# CR-10_Motherboard_1.net
KiCad netlist of a schematic drawn in Altium Designer
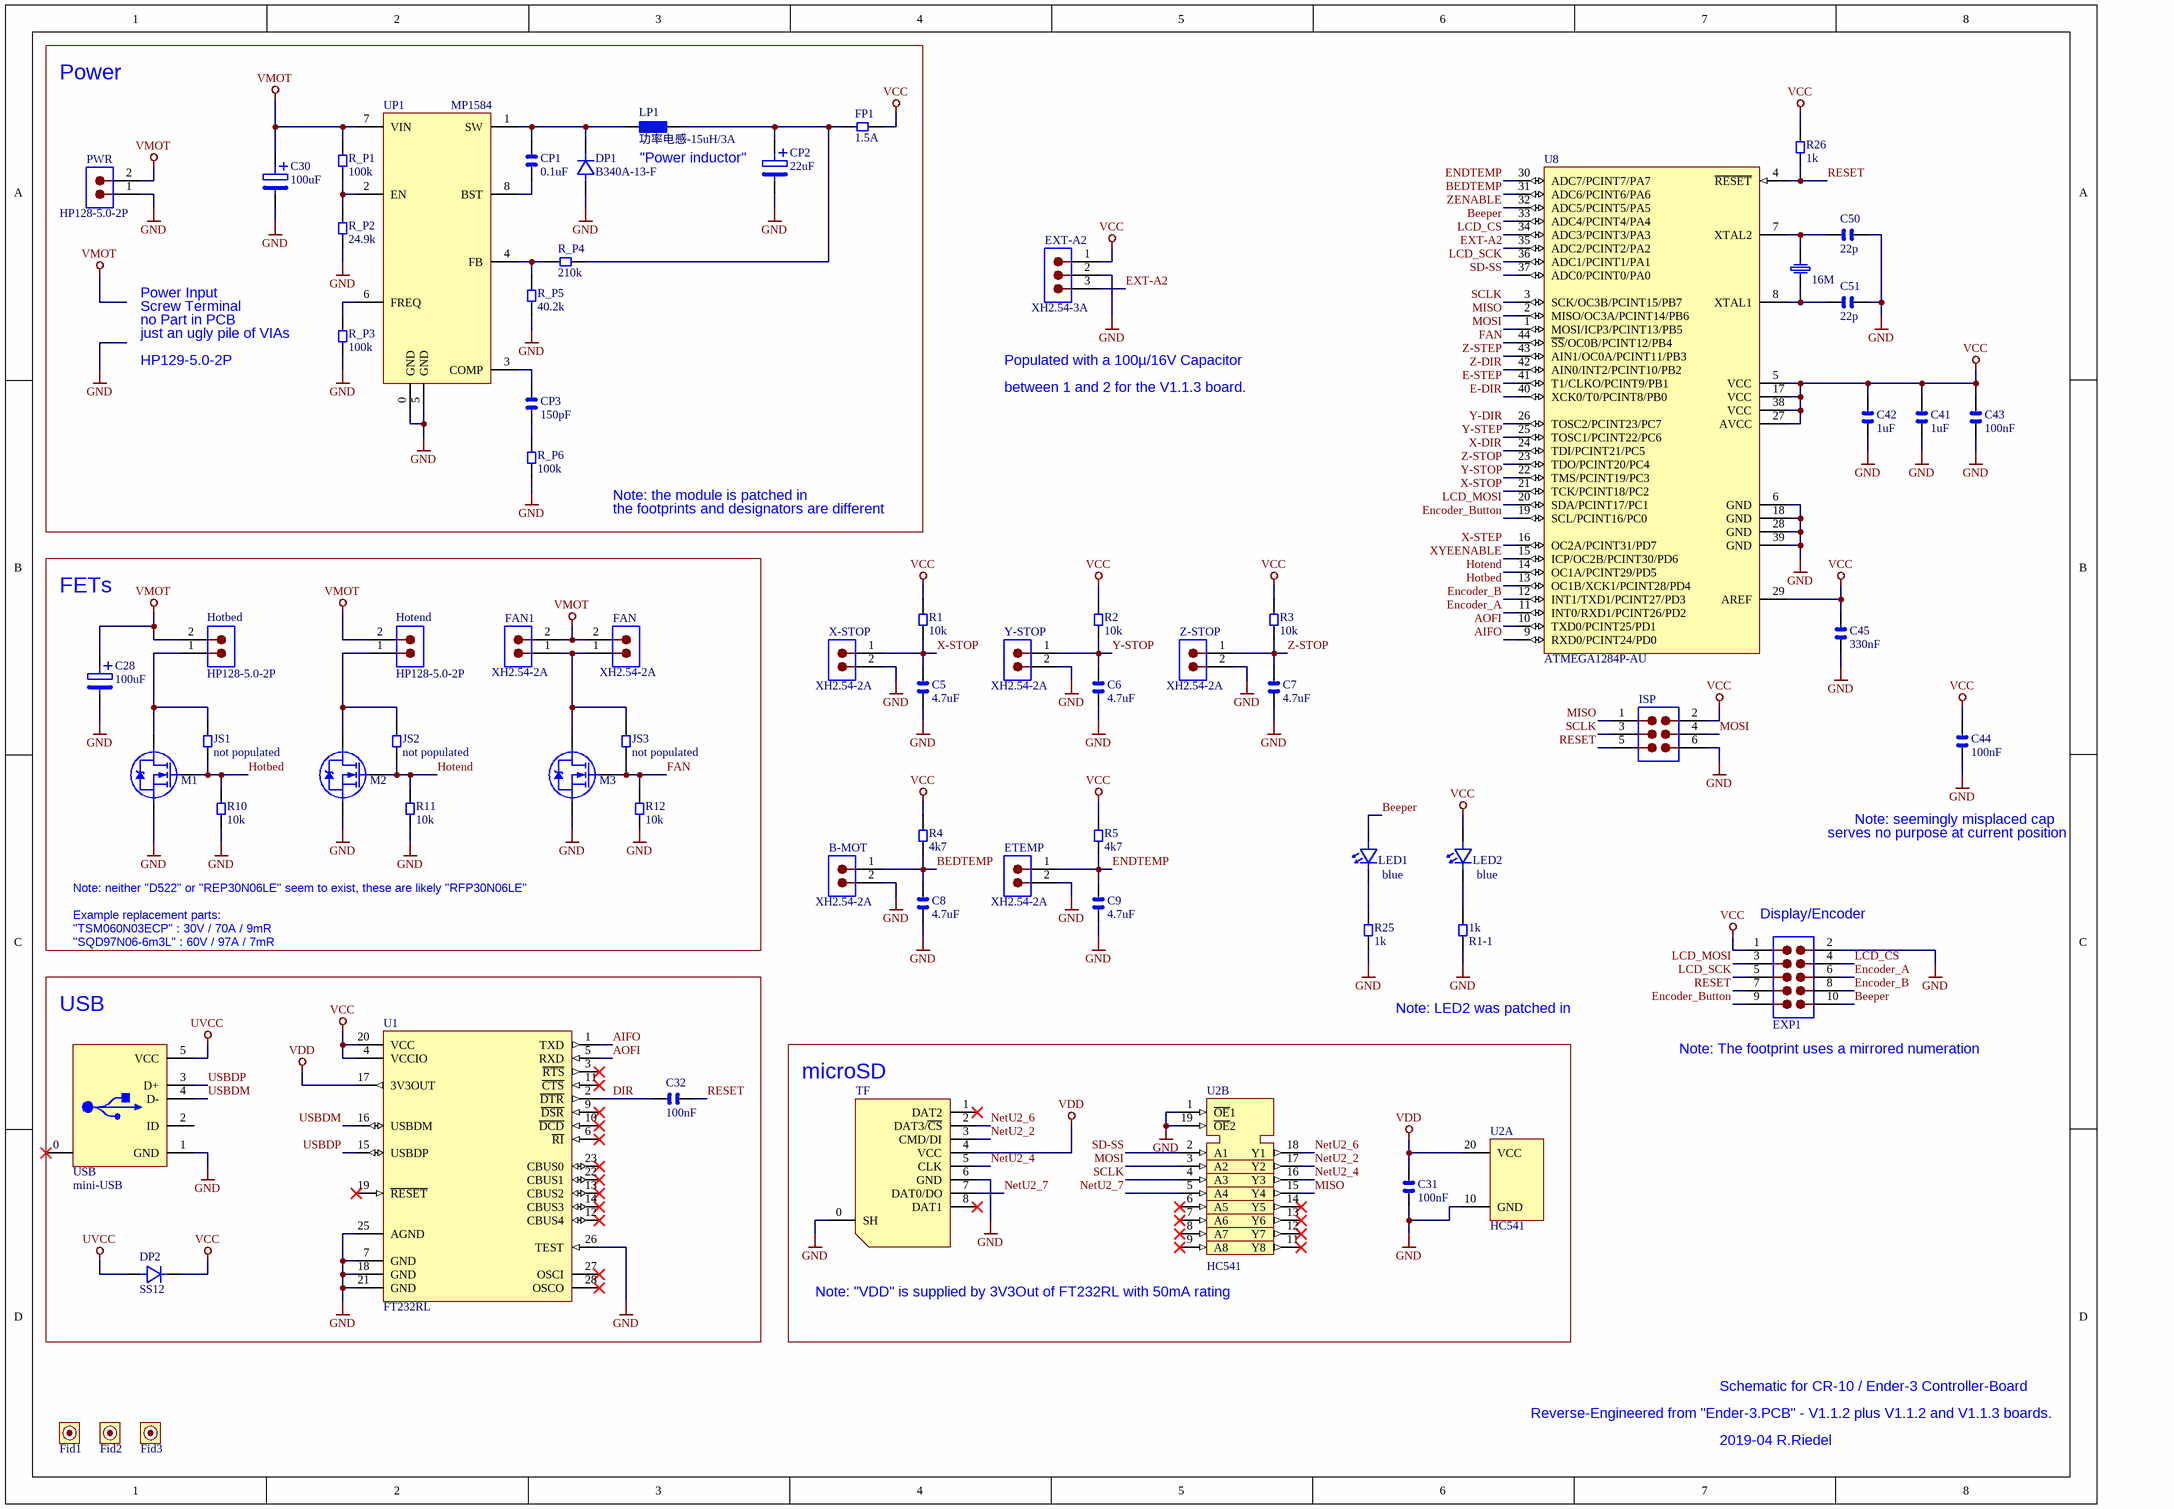
[diagram p0: CR-10 Motherboard_1.SchDoc]

(export (version "E")
  (design (tool "Eeschema 10.0.6"))
  (components
    (comp (ref "1k")
      (value "R1-1")
      (footprint "Ender3:0603")
      (description "0603 Chip Resistor")
      (libsource (lib "CR-10 Motherboard") (part "Resistor"))
    )
    (comp (ref "16M")
      (value "16Mhz")
      (footprint "Ender3:CRY")
      (description "Crystal HC49/US")
      (libsource (lib "CR-10 Motherboard") (part "Crystal"))
    )
    (comp (ref "B-MOT")
      (value "XH2.54-2A")
      (footprint "Ender3:P2")
      (description "Header 1x2")
      (libsource (lib "CR-10 Motherboard") (part "Header 1x2"))
    )
    (comp (ref "C5")
      (value "4.7uF")
      (footprint "Ender3:0805")
      (description "0805 Chip Capacitor")
      (libsource (lib "CR-10 Motherboard") (part "CAP_2_V2"))
    )
    (comp (ref "C6")
      (value "4.7uF")
      (footprint "Ender3:0805")
      (description "0805 Chip Capacitor")
      (libsource (lib "CR-10 Motherboard") (part "CAP_2_V2"))
    )
    (comp (ref "C7")
      (value "4.7uF")
      (footprint "Ender3:0805")
      (description "0805 Chip Capacitor")
      (libsource (lib "CR-10 Motherboard") (part "CAP_2_V2"))
    )
    (comp (ref "C8")
      (value "4.7uF")
      (footprint "Ender3:0805")
      (description "0805 Chip Capacitor")
      (libsource (lib "CR-10 Motherboard") (part "CAP_2_V2"))
    )
    (comp (ref "C9")
      (value "4.7uF")
      (footprint "Ender3:0805")
      (description "0805 Chip Capacitor")
      (libsource (lib "CR-10 Motherboard") (part "CAP_2_V2"))
    )
    (comp (ref "C28")
      (value "100uF")
      (footprint "Ender3:CAP-100")
      (description "Capacitor Polarized")
      (libsource (lib "CR-10 Motherboard") (part "Capacitor Pol"))
    )
    (comp (ref "C30")
      (value "100uF")
      (footprint "Ender3:CAP-100")
      (description "Capacitor Polarized")
      (libsource (lib "CR-10 Motherboard") (part "Capacitor Pol"))
    )
    (comp (ref "C31")
      (value "100nF")
      (footprint "Ender3:0805")
      (description "0805 Chip Capacitor")
      (libsource (lib "CR-10 Motherboard") (part "Capacitor"))
    )
    (comp (ref "C32")
      (value "100nF")
      (footprint "Ender3:0603")
      (description "0805 Chip Capacitor")
      (libsource (lib "CR-10 Motherboard") (part "Capacitor"))
    )
    (comp (ref "C41")
      (value "1uF")
      (footprint "Ender3:0603")
      (description "0805 Chip Capacitor")
      (libsource (lib "CR-10 Motherboard") (part "Capacitor"))
    )
    (comp (ref "C42")
      (value "1uF")
      (footprint "Ender3:0603")
      (description "0805 Chip Capacitor")
      (libsource (lib "CR-10 Motherboard") (part "Capacitor"))
    )
    (comp (ref "C43")
      (value "100nF")
      (footprint "Ender3:0603")
      (description "0805 Chip Capacitor")
      (libsource (lib "CR-10 Motherboard") (part "Capacitor"))
    )
    (comp (ref "C44")
      (value "100nF")
      (footprint "Ender3:0603")
      (description "0805 Chip Capacitor")
      (libsource (lib "CR-10 Motherboard") (part "Capacitor"))
    )
    (comp (ref "C45")
      (value "330nF")
      (footprint "0603")
      (description "0805 Chip Capacitor")
      (libsource (lib "CR-10 Motherboard") (part "Capacitor"))
    )
    (comp (ref "C50")
      (value "22p")
      (footprint "Ender3:0603")
      (description "0805 Chip Capacitor")
      (libsource (lib "CR-10 Motherboard") (part "Capacitor"))
    )
    (comp (ref "C51")
      (value "22p")
      (footprint "Ender3:0603")
      (description "0805 Chip Capacitor")
      (libsource (lib "CR-10 Motherboard") (part "Capacitor"))
    )
    (comp (ref "CP1")
      (value "0.1uF")
      (footprint "Ender3:C0603")
      (description "Chip Capacitor")
      (libsource (lib "CR-10 Motherboard") (part "Capacitor"))
    )
    (comp (ref "CP2")
      (value "22uF")
      (footprint "Ender3:RVT4X5.5")
      (description "Capacitor Polarized")
      (libsource (lib "CR-10 Motherboard") (part "Capacitor Pol"))
    )
    (comp (ref "CP3")
      (value "150pF")
      (footprint "Ender3:C0603")
      (description "Chip Capacitor")
      (libsource (lib "CR-10 Motherboard") (part "Capacitor"))
    )
    (comp (ref "DP1")
      (value "B340A-13-F")
      (footprint "Ender3:D-SMA")
      (description "Diode")
      (libsource (lib "CR-10 Motherboard") (part "Diode_A1_K2"))
    )
    (comp (ref "DP2")
      (value "SS12")
      (footprint "Ender3:D-SMA")
      (description "Diode")
      (libsource (lib "CR-10 Motherboard") (part "Diode_A1_K2"))
    )
    (comp (ref "ETEMP")
      (value "XH2.54-2A")
      (footprint "Ender3:P2")
      (description "Header 1x2")
      (libsource (lib "CR-10 Motherboard") (part "Header 1x2"))
    )
    (comp (ref "EXP1")
      (value "Header 2x5")
      (footprint "Ender3:SOP10")
      (libsource (lib "CR-10 Motherboard") (part "Header 2x5"))
    )
    (comp (ref "EXT-A2")
      (value "XH2.54-3A")
      (footprint "Ender3:XH-3A")
      (description "Header 1x3")
      (libsource (lib "CR-10 Motherboard") (part "Header 1x3"))
    )
    (comp (ref "FAN")
      (value "XH2.54-2A")
      (footprint "Ender3:P2")
      (description "Header 1x2")
      (libsource (lib "CR-10 Motherboard") (part "Header 1x2"))
    )
    (comp (ref "FAN1")
      (value "XH2.54-2A")
      (footprint "Ender3:P2")
      (description "Header 1x2")
      (libsource (lib "CR-10 Motherboard") (part "Header 1x2"))
    )
    (comp (ref "Fid1")
      (value "Fiducial")
      (footprint "Ender3:Fiducial-A")
      (libsource (lib "CR-10 Motherboard") (part "Fiducial"))
    )
    (comp (ref "Fid2")
      (value "Fiducial")
      (footprint "Ender3:Fiducial-A")
      (libsource (lib "CR-10 Motherboard") (part "Fiducial"))
    )
    (comp (ref "Fid3")
      (value "Fiducial")
      (footprint "Ender3:Fiducial-A")
      (libsource (lib "CR-10 Motherboard") (part "Fiducial"))
    )
    (comp (ref "FP1")
      (value "1.5A")
      (footprint "Ender3:MF-MSMF050")
      (description "Chip Resistor")
      (libsource (lib "CR-10 Motherboard") (part "Resistor"))
    )
    (comp (ref "Hotbed")
      (value "HP128-5.0-2P")
      (footprint "CR-10 Motherboard:MOT-2")
      (description "Terminal 1x2")
      (libsource (lib "CR-10 Motherboard") (part "Header 1x2"))
    )
    (comp (ref "Hotend")
      (value "HP128-5.0-2P")
      (footprint "CR-10 Motherboard:MOT-2")
      (description "Terminal 1x2")
      (libsource (lib "CR-10 Motherboard") (part "Header 1x2"))
    )
    (comp (ref "ISP")
      (value "HEADER 3X2")
      (description "Header 2x3")
      (libsource (lib "CR-10 Motherboard") (part "Header 2x3"))
    )
    (comp (ref "JS1")
      (value "not populated")
      (footprint "Ender3:R10")
      (description "0603 Chip Resistor")
      (libsource (lib "CR-10 Motherboard") (part "Resistor"))
    )
    (comp (ref "JS2")
      (value "not populated")
      (footprint "Ender3:R10")
      (description "0603 Chip Resistor")
      (libsource (lib "CR-10 Motherboard") (part "Resistor"))
    )
    (comp (ref "JS3")
      (value "not populated")
      (footprint "Ender3:R10")
      (description "0603 Chip Resistor")
      (libsource (lib "CR-10 Motherboard") (part "Resistor"))
    )
    (comp (ref "LED1")
      (value "blue")
      (footprint "Ender3:0603")
      (description "LED")
      (libsource (lib "CR-10 Motherboard") (part "LED_A1C2"))
    )
    (comp (ref "LED2")
      (value "blue")
      (footprint "Ender3:0603")
      (description "LED")
      (libsource (lib "CR-10 Motherboard") (part "LED_C1A2"))
    )
    (comp (ref "LP1")
      (value "功率电感-15uH/3A")
      (footprint "Ender3:DO3316P")
      (description "Inductor")
      (libsource (lib "CR-10 Motherboard") (part "Inductor"))
    )
    (comp (ref "M1")
      (value "REP30N06LE")
      (footprint "Ender3:TO-252")
      (description "N-FET")
      (libsource (lib "CR-10 Motherboard") (part "N-FET"))
    )
    (comp (ref "M2")
      (value "REP30N06LE")
      (footprint "Ender3:TO-252")
      (description "N-FET")
      (libsource (lib "CR-10 Motherboard") (part "N-FET"))
    )
    (comp (ref "M3")
      (value "REP30N06LE")
      (footprint "Ender3:TO-252")
      (description "N-FET")
      (libsource (lib "CR-10 Motherboard") (part "N-FET"))
    )
    (comp (ref "PWR")
      (value "HP128-5.0-2P")
      (footprint "CR-10 Motherboard:MOT-2")
      (description "Terminal 1x2")
      (libsource (lib "CR-10 Motherboard") (part "Header 1x2"))
    )
    (comp (ref "R1")
      (value "10k")
      (footprint "Ender3:0603")
      (description "0603 Chip Resistor")
      (libsource (lib "CR-10 Motherboard") (part "RES_2_V2"))
    )
    (comp (ref "R2")
      (value "10k")
      (footprint "Ender3:0603")
      (description "0603 Chip Resistor")
      (libsource (lib "CR-10 Motherboard") (part "RES_2_V2"))
    )
    (comp (ref "R3")
      (value "10k")
      (footprint "Ender3:0603")
      (description "0603 Chip Resistor")
      (libsource (lib "CR-10 Motherboard") (part "RES_2_V2"))
    )
    (comp (ref "R4")
      (value "4k7")
      (footprint "Ender3:0603")
      (description "0603 Chip Resistor")
      (libsource (lib "CR-10 Motherboard") (part "RES_2_V2"))
    )
    (comp (ref "R5")
      (value "4k7")
      (footprint "Ender3:0603")
      (description "0603 Chip Resistor")
      (libsource (lib "CR-10 Motherboard") (part "RES_2_V2"))
    )
    (comp (ref "R10")
      (value "10k")
      (footprint "Ender3:0603")
      (description "0603 Chip Resistor")
      (libsource (lib "CR-10 Motherboard") (part "Resistor"))
    )
    (comp (ref "R11")
      (value "10k")
      (footprint "Ender3:0603")
      (description "0603 Chip Resistor")
      (libsource (lib "CR-10 Motherboard") (part "Resistor"))
    )
    (comp (ref "R12")
      (value "10k")
      (footprint "Ender3:0603")
      (description "0603 Chip Resistor")
      (libsource (lib "CR-10 Motherboard") (part "Resistor"))
    )
    (comp (ref "R25")
      (value "1k")
      (footprint "Ender3:0603")
      (description "0603 Chip Resistor")
      (libsource (lib "CR-10 Motherboard") (part "Resistor"))
    )
    (comp (ref "R26")
      (value "1k")
      (footprint "Ender3:0603")
      (description "0603 Chip Resistor")
      (libsource (lib "CR-10 Motherboard") (part "Resistor"))
    )
    (comp (ref "R_P1")
      (value "100k")
      (footprint "Ender3:R0603")
      (description "0603 Chip Resistor")
      (libsource (lib "CR-10 Motherboard") (part "Resistor"))
    )
    (comp (ref "R_P2")
      (value "24.9k")
      (footprint "Ender3:R0603")
      (description "Chip Resistor")
      (libsource (lib "CR-10 Motherboard") (part "Resistor"))
    )
    (comp (ref "R_P3")
      (value "100k")
      (footprint "Ender3:R0603")
      (description "0603 Chip Resistor")
      (libsource (lib "CR-10 Motherboard") (part "Resistor"))
    )
    (comp (ref "R_P4")
      (value "210k")
      (footprint "Ender3:R0603")
      (description "0603 Chip Resistor")
      (libsource (lib "CR-10 Motherboard") (part "Resistor"))
    )
    (comp (ref "R_P5")
      (value "40.2k")
      (footprint "Ender3:R0603")
      (description "0603 Chip Resistor")
      (libsource (lib "CR-10 Motherboard") (part "Resistor"))
    )
    (comp (ref "R_P6")
      (value "100k")
      (footprint "Ender3:R0603")
      (description "0603 Chip Resistor")
      (libsource (lib "CR-10 Motherboard") (part "Resistor"))
    )
    (comp (ref "TF")
      (value "TF")
      (footprint "Ender3:TF")
      (description "microSD")
      (libsource (lib "CR-10 Motherboard") (part "microSD"))
    )
    (comp (ref "U1")
      (value "FT232RL")
      (footprint "Ender3:PL2303")
      (description "FTDI USB UART I.C.")
      (libsource (lib "CR-10 Motherboard") (part "FT232RL"))
    )
    (comp (ref "U2")
      (value "HC541")
      (footprint "Ender3:SSOP-20")
      (description "74HC541 - Octal buffer/line driver")
      (libsource (lib "CR-10 Motherboard") (part "74HC541"))
    )
    (comp (ref "U8")
      (value "ATMEGA1284P-AU")
      (footprint "Ender3:QFP-44")
      (description "AVR 8-Bit, 128k FLASH, TQFP44")
      (fields (field (name "PART NUMBER") "ATmega1284P-AU"))
      (libsource (lib "CR-10 Motherboard") (part "ATmegaxx4PA-xx"))
    )
    (comp (ref "UP1")
      (value "MP1584")
      (footprint "Ender3:SOIC8E")
      (libsource (lib "CR-10 Motherboard") (part "MP1584"))
    )
    (comp (ref "USB")
      (value "mini-USB")
      (footprint "Ender3:USB")
      (description "USB")
      (libsource (lib "CR-10 Motherboard") (part "USB"))
    )
    (comp (ref "X-STOP")
      (value "XH2.54-2A")
      (footprint "Ender3:P2")
      (description "Header 1x2")
      (libsource (lib "CR-10 Motherboard") (part "Header 1x2"))
    )
    (comp (ref "Y-STOP")
      (value "XH2.54-2A")
      (footprint "Ender3:P2")
      (description "Header 1x2")
      (libsource (lib "CR-10 Motherboard") (part "Header 1x2"))
    )
    (comp (ref "Z-STOP")
      (value "XH2.54-2A")
      (footprint "Ender3:P2")
      (description "Header 1x2")
      (libsource (lib "CR-10 Motherboard") (part "Header 1x2"))
    )
  )
  (nets
    (net (code "1") (name "/AIFO") (class "Default")
      (node (ref "U1") (pin "1") (pinfunction "TXD_1") (pintype "output"))
      (node (ref "U8") (pin "9") (pinfunction "RXD0/PCINT24/PD0_9") (pintype "bidirectional"))
    )
    (net (code "2") (name "/AOFI") (class "Default")
      (node (ref "U1") (pin "5") (pinfunction "RXD_5") (pintype "input"))
      (node (ref "U8") (pin "10") (pinfunction "TXD0/PCINT25/PD1_10") (pintype "bidirectional"))
    )
    (net (code "3") (name "/BEDTEMP") (class "Default")
      (node (ref "B-MOT") (pin "1") (pinfunction "1_1") (pintype "passive"))
      (node (ref "C8") (pin "1") (pinfunction "1_1") (pintype "passive"))
      (node (ref "R4") (pin "1") (pinfunction "1_1") (pintype "passive"))
      (node (ref "U8") (pin "31") (pinfunction "ADC6/PCINT6/PA6_31") (pintype "bidirectional"))
    )
    (net (code "4") (name "/Beeper") (class "Default")
      (node (ref "EXP1") (pin "10") (pinfunction "10_10") (pintype "passive"))
      (node (ref "LED1") (pin "1") (pinfunction "1_1") (pintype "passive"))
      (node (ref "U8") (pin "33") (pinfunction "ADC4/PCINT4/PA4_33") (pintype "bidirectional"))
    )
    (net (code "5") (name "/DIR") (class "Default")
      (node (ref "C32") (pin "1") (pinfunction "1_1") (pintype "passive"))
      (node (ref "U1") (pin "2") (pinfunction "~{DTR}_2") (pintype "output"))
    )
    (net (code "6") (name "/E-DIR") (class "Default")
      (node (ref "U8") (pin "40") (pinfunction "XCK0/T0/PCINT8/PB0_40") (pintype "bidirectional"))
    )
    (net (code "7") (name "/E-STEP") (class "Default")
      (node (ref "U8") (pin "41") (pinfunction "T1/CLKO/PCINT9/PB1_41") (pintype "bidirectional"))
    )
    (net (code "8") (name "/ENDTEMP") (class "Default")
      (node (ref "C9") (pin "1") (pinfunction "1_1") (pintype "passive"))
      (node (ref "ETEMP") (pin "1") (pinfunction "1_1") (pintype "passive"))
      (node (ref "R5") (pin "1") (pinfunction "1_1") (pintype "passive"))
      (node (ref "U8") (pin "30") (pinfunction "ADC7/PCINT7/PA7_30") (pintype "bidirectional"))
    )
    (net (code "9") (name "/EXT-A2") (class "Default")
      (node (ref "EXT-A2") (pin "3") (pinfunction "3_3") (pintype "passive"))
      (node (ref "U8") (pin "35") (pinfunction "ADC2/PCINT2/PA2_35") (pintype "bidirectional"))
    )
    (net (code "10") (name "/Encoder_A") (class "Default")
      (node (ref "EXP1") (pin "6") (pinfunction "6_6") (pintype "passive"))
      (node (ref "U8") (pin "11") (pinfunction "INT0/RXD1/PCINT26/PD2_11") (pintype "bidirectional"))
    )
    (net (code "11") (name "/Encoder_B") (class "Default")
      (node (ref "EXP1") (pin "8") (pinfunction "8_8") (pintype "passive"))
      (node (ref "U8") (pin "12") (pinfunction "INT1/TXD1/PCINT27/PD3_12") (pintype "bidirectional"))
    )
    (net (code "12") (name "/Encoder_Button") (class "Default")
      (node (ref "EXP1") (pin "9") (pinfunction "9_9") (pintype "passive"))
      (node (ref "U8") (pin "19") (pinfunction "SCL/PCINT16/PC0_19") (pintype "bidirectional"))
    )
    (net (code "13") (name "/FAN") (class "Default")
      (node (ref "JS3") (pin "1") (pinfunction "1_1") (pintype "passive"))
      (node (ref "M3") (pin "1") (pinfunction "G_1") (pintype "passive"))
      (node (ref "R12") (pin "1") (pinfunction "1_1") (pintype "passive"))
      (node (ref "U8") (pin "44") (pinfunction "~{SS}/OC0B/PCINT12/PB4_44") (pintype "bidirectional"))
    )
    (net (code "14") (name "/Hotbed") (class "Default")
      (node (ref "JS1") (pin "1") (pinfunction "1_1") (pintype "passive"))
      (node (ref "M1") (pin "1") (pinfunction "G_1") (pintype "passive"))
      (node (ref "R10") (pin "1") (pinfunction "1_1") (pintype "passive"))
      (node (ref "U8") (pin "13") (pinfunction "OC1B/XCK1/PCINT28/PD4_13") (pintype "bidirectional"))
    )
    (net (code "15") (name "/Hotend") (class "Default")
      (node (ref "JS2") (pin "1") (pinfunction "1_1") (pintype "passive"))
      (node (ref "M2") (pin "1") (pinfunction "G_1") (pintype "passive"))
      (node (ref "R11") (pin "1") (pinfunction "1_1") (pintype "passive"))
      (node (ref "U8") (pin "14") (pinfunction "OC1A/PCINT29/PD5_14") (pintype "bidirectional"))
    )
    (net (code "16") (name "/LCD_CS") (class "Default")
      (node (ref "EXP1") (pin "4") (pinfunction "4_4") (pintype "passive"))
      (node (ref "U8") (pin "34") (pinfunction "ADC3/PCINT3/PA3_34") (pintype "bidirectional"))
    )
    (net (code "17") (name "/LCD_MOSI") (class "Default")
      (node (ref "EXP1") (pin "3") (pinfunction "3_3") (pintype "passive"))
      (node (ref "U8") (pin "20") (pinfunction "SDA/PCINT17/PC1_20") (pintype "bidirectional"))
    )
    (net (code "18") (name "/LCD_SCK") (class "Default")
      (node (ref "EXP1") (pin "5") (pinfunction "5_5") (pintype "passive"))
      (node (ref "U8") (pin "36") (pinfunction "ADC1/PCINT1/PA1_36") (pintype "bidirectional"))
    )
    (net (code "19") (name "/MISO") (class "Default")
      (node (ref "ISP") (pin "1") (pinfunction "1_1") (pintype "passive"))
      (node (ref "U2") (pin "15") (pinfunction "Y4_15") (pintype "output"))
      (node (ref "U8") (pin "2") (pinfunction "MISO/OC3A/PCINT14/PB6_2") (pintype "bidirectional"))
    )
    (net (code "20") (name "/MOSI") (class "Default")
      (node (ref "ISP") (pin "4") (pinfunction "4_4") (pintype "passive"))
      (node (ref "U2") (pin "3") (pinfunction "A2_3") (pintype "input"))
      (node (ref "U8") (pin "1") (pinfunction "MOSI/ICP3/PCINT13/PB5_1") (pintype "bidirectional"))
    )
    (net (code "21") (name "/NetU2_2") (class "Default")
      (node (ref "TF") (pin "3") (pinfunction "CMD/DI_3") (pintype "passive"))
      (node (ref "U2") (pin "17") (pinfunction "Y2_17") (pintype "output"))
    )
    (net (code "22") (name "/NetU2_4") (class "Default")
      (node (ref "TF") (pin "5") (pinfunction "CLK_5") (pintype "passive"))
      (node (ref "U2") (pin "16") (pinfunction "Y3_16") (pintype "output"))
    )
    (net (code "23") (name "/NetU2_6") (class "Default")
      (node (ref "TF") (pin "2") (pinfunction "DAT3/~{CS}_2") (pintype "passive"))
      (node (ref "U2") (pin "18") (pinfunction "Y1_18") (pintype "output"))
    )
    (net (code "24") (name "/NetU2_7") (class "Default")
      (node (ref "TF") (pin "7") (pinfunction "DAT0/DO_7") (pintype "passive"))
      (node (ref "U2") (pin "5") (pinfunction "A4_5") (pintype "input"))
    )
    (net (code "25") (name "/RESET") (class "Default")
      (node (ref "C32") (pin "2") (pinfunction "2_2") (pintype "passive"))
      (node (ref "EXP1") (pin "7") (pinfunction "7_7") (pintype "passive"))
      (node (ref "ISP") (pin "5") (pinfunction "5_5") (pintype "passive"))
      (node (ref "R26") (pin "1") (pinfunction "1_1") (pintype "passive"))
      (node (ref "U8") (pin "4") (pinfunction "~{RESET}_4") (pintype "input"))
    )
    (net (code "26") (name "/SCLK") (class "Default")
      (node (ref "ISP") (pin "3") (pinfunction "3_3") (pintype "passive"))
      (node (ref "U2") (pin "4") (pinfunction "A3_4") (pintype "input"))
      (node (ref "U8") (pin "3") (pinfunction "SCK/OC3B/PCINT15/PB7_3") (pintype "bidirectional"))
    )
    (net (code "27") (name "/SD-SS") (class "Default")
      (node (ref "U2") (pin "2") (pinfunction "A1_2") (pintype "input"))
      (node (ref "U8") (pin "37") (pinfunction "ADC0/PCINT0/PA0_37") (pintype "bidirectional"))
    )
    (net (code "28") (name "/USBDM") (class "Default")
      (node (ref "U1") (pin "16") (pinfunction "USBDM_16") (pintype "bidirectional"))
      (node (ref "USB") (pin "4") (pinfunction "D-_4") (pintype "passive"))
    )
    (net (code "29") (name "/USBDP") (class "Default")
      (node (ref "U1") (pin "15") (pinfunction "USBDP_15") (pintype "bidirectional"))
      (node (ref "USB") (pin "3") (pinfunction "D+_3") (pintype "passive"))
    )
    (net (code "30") (name "/X-DIR") (class "Default")
      (node (ref "U8") (pin "24") (pinfunction "TDI/PCINT21/PC5_24") (pintype "bidirectional"))
    )
    (net (code "31") (name "/X-STEP") (class "Default")
      (node (ref "U8") (pin "16") (pinfunction "OC2A/PCINT31/PD7_16") (pintype "bidirectional"))
    )
    (net (code "32") (name "/X-STOP") (class "Default")
      (node (ref "C5") (pin "1") (pinfunction "1_1") (pintype "passive"))
      (node (ref "R1") (pin "1") (pinfunction "1_1") (pintype "passive"))
      (node (ref "U8") (pin "21") (pinfunction "TCK/PCINT18/PC2_21") (pintype "bidirectional"))
      (node (ref "X-STOP") (pin "1") (pinfunction "1_1") (pintype "passive"))
    )
    (net (code "33") (name "/XYEENABLE") (class "Default")
      (node (ref "U8") (pin "15") (pinfunction "ICP/OC2B/PCINT30/PD6_15") (pintype "bidirectional"))
    )
    (net (code "34") (name "/Y-DIR") (class "Default")
      (node (ref "U8") (pin "26") (pinfunction "TOSC2/PCINT23/PC7_26") (pintype "bidirectional"))
    )
    (net (code "35") (name "/Y-STEP") (class "Default")
      (node (ref "U8") (pin "25") (pinfunction "TOSC1/PCINT22/PC6_25") (pintype "bidirectional"))
    )
    (net (code "36") (name "/Y-STOP") (class "Default")
      (node (ref "C6") (pin "1") (pinfunction "1_1") (pintype "passive"))
      (node (ref "R2") (pin "1") (pinfunction "1_1") (pintype "passive"))
      (node (ref "U8") (pin "22") (pinfunction "TMS/PCINT19/PC3_22") (pintype "bidirectional"))
      (node (ref "Y-STOP") (pin "1") (pinfunction "1_1") (pintype "passive"))
    )
    (net (code "37") (name "/Z-DIR") (class "Default")
      (node (ref "U8") (pin "42") (pinfunction "AIN0/INT2/PCINT10/PB2_42") (pintype "bidirectional"))
    )
    (net (code "38") (name "/Z-STEP") (class "Default")
      (node (ref "U8") (pin "43") (pinfunction "AIN1/OC0A/PCINT11/PB3_43") (pintype "bidirectional"))
    )
    (net (code "39") (name "/Z-STOP") (class "Default")
      (node (ref "C7") (pin "1") (pinfunction "1_1") (pintype "passive"))
      (node (ref "R3") (pin "1") (pinfunction "1_1") (pintype "passive"))
      (node (ref "U8") (pin "23") (pinfunction "TDO/PCINT20/PC4_23") (pintype "bidirectional"))
      (node (ref "Z-STOP") (pin "1") (pinfunction "1_1") (pintype "passive"))
    )
    (net (code "40") (name "/ZENABLE") (class "Default")
      (node (ref "U8") (pin "32") (pinfunction "ADC5/PCINT5/PA5_32") (pintype "bidirectional"))
    )
    (net (code "41") (name "GND") (class "Default")
      (node (ref "1k") (pin "2") (pinfunction "2_2") (pintype "passive"))
      (node (ref "B-MOT") (pin "2") (pinfunction "2_2") (pintype "passive"))
      (node (ref "C28") (pin "2") (pinfunction "2_2") (pintype "passive"))
      (node (ref "C30") (pin "2") (pinfunction "2_2") (pintype "passive"))
      (node (ref "C31") (pin "2") (pinfunction "2_2") (pintype "passive"))
      (node (ref "C41") (pin "2") (pinfunction "2_2") (pintype "passive"))
      (node (ref "C42") (pin "2") (pinfunction "2_2") (pintype "passive"))
      (node (ref "C43") (pin "2") (pinfunction "2_2") (pintype "passive"))
      (node (ref "C44") (pin "2") (pinfunction "2_2") (pintype "passive"))
      (node (ref "C45") (pin "2") (pinfunction "2_2") (pintype "passive"))
      (node (ref "C5") (pin "2") (pinfunction "2_2") (pintype "passive"))
      (node (ref "C50") (pin "2") (pinfunction "2_2") (pintype "passive"))
      (node (ref "C51") (pin "2") (pinfunction "2_2") (pintype "passive"))
      (node (ref "C6") (pin "2") (pinfunction "2_2") (pintype "passive"))
      (node (ref "C7") (pin "2") (pinfunction "2_2") (pintype "passive"))
      (node (ref "C8") (pin "2") (pinfunction "2_2") (pintype "passive"))
      (node (ref "C9") (pin "2") (pinfunction "2_2") (pintype "passive"))
      (node (ref "CP2") (pin "2") (pinfunction "2_2") (pintype "passive"))
      (node (ref "DP1") (pin "1") (pinfunction "1_1") (pintype "passive"))
      (node (ref "ETEMP") (pin "2") (pinfunction "2_2") (pintype "passive"))
      (node (ref "EXP1") (pin "2") (pinfunction "2_2") (pintype "passive"))
      (node (ref "EXT-A2") (pin "2") (pinfunction "2_2") (pintype "passive"))
      (node (ref "ISP") (pin "6") (pinfunction "6_6") (pintype "passive"))
      (node (ref "M1") (pin "3") (pinfunction "S_3") (pintype "passive"))
      (node (ref "M2") (pin "3") (pinfunction "S_3") (pintype "passive"))
      (node (ref "M3") (pin "3") (pinfunction "S_3") (pintype "passive"))
      (node (ref "PWR") (pin "1") (pinfunction "1_1") (pintype "passive"))
      (node (ref "R10") (pin "2") (pinfunction "2_2") (pintype "passive"))
      (node (ref "R11") (pin "2") (pinfunction "2_2") (pintype "passive"))
      (node (ref "R12") (pin "2") (pinfunction "2_2") (pintype "passive"))
      (node (ref "R25") (pin "2") (pinfunction "2_2") (pintype "passive"))
      (node (ref "R_P2") (pin "2") (pinfunction "2_2") (pintype "passive"))
      (node (ref "R_P3") (pin "2") (pinfunction "2_2") (pintype "passive"))
      (node (ref "R_P5") (pin "2") (pinfunction "2_2") (pintype "passive"))
      (node (ref "R_P6") (pin "2") (pinfunction "2_2") (pintype "passive"))
      (node (ref "TF") (pin "0") (pinfunction "SH_0") (pintype "passive"))
      (node (ref "TF") (pin "6") (pinfunction "GND_6") (pintype "passive"))
      (node (ref "U1") (pin "18") (pinfunction "GND_18") (pintype "power_in"))
      (node (ref "U1") (pin "21") (pinfunction "GND_21") (pintype "power_in"))
      (node (ref "U1") (pin "25") (pinfunction "AGND_25") (pintype "power_in"))
      (node (ref "U1") (pin "26") (pinfunction "TEST_26") (pintype "input"))
      (node (ref "U1") (pin "7") (pinfunction "GND_7") (pintype "power_in"))
      (node (ref "U2") (pin "1") (pinfunction "~{OE}1_1") (pintype "input"))
      (node (ref "U2") (pin "10") (pinfunction "GND_10") (pintype "power_in"))
      (node (ref "U2") (pin "19") (pinfunction "~{OE}2_19") (pintype "input"))
      (node (ref "U8") (pin "18") (pinfunction "GND_18") (pintype "power_in"))
      (node (ref "U8") (pin "28") (pinfunction "GND_28") (pintype "power_in"))
      (node (ref "U8") (pin "39") (pinfunction "GND_39") (pintype "power_in"))
      (node (ref "U8") (pin "6") (pinfunction "GND_6") (pintype "power_in"))
      (node (ref "UP1") (pin "0") (pinfunction "GND_0") (pintype "passive"))
      (node (ref "UP1") (pin "5") (pinfunction "GND_5") (pintype "passive"))
      (node (ref "USB") (pin "1") (pinfunction "GND_1") (pintype "passive"))
      (node (ref "X-STOP") (pin "2") (pinfunction "2_2") (pintype "passive"))
      (node (ref "Y-STOP") (pin "2") (pinfunction "2_2") (pintype "passive"))
      (node (ref "Z-STOP") (pin "2") (pinfunction "2_2") (pintype "passive"))
    )
    (net (code "42") (name "Net-(1k-Pad1)") (class "Default")
      (node (ref "1k") (pin "1") (pinfunction "1_1") (pintype "passive"))
      (node (ref "LED2") (pin "1") (pinfunction "1_1") (pintype "passive"))
    )
    (net (code "43") (name "Net-(CP2-Pad1)") (class "Default")
      (node (ref "CP2") (pin "1") (pinfunction "1_1") (pintype "passive"))
      (node (ref "FP1") (pin "1") (pinfunction "1_1") (pintype "passive"))
      (node (ref "LP1") (pin "1") (pinfunction "1_1") (pintype "passive"))
      (node (ref "R_P4") (pin "2") (pinfunction "2_2") (pintype "passive"))
    )
    (net (code "44") (name "Net-(CP3-Pad1)") (class "Default")
      (node (ref "CP3") (pin "1") (pinfunction "1_1") (pintype "passive"))
      (node (ref "R_P6") (pin "1") (pinfunction "1_1") (pintype "passive"))
    )
    (net (code "45") (name "Net-(LED1-Pad2)") (class "Default")
      (node (ref "LED1") (pin "2") (pinfunction "2_2") (pintype "passive"))
      (node (ref "R25") (pin "1") (pinfunction "1_1") (pintype "passive"))
    )
    (net (code "46") (name "Net-(M1-D)") (class "Default")
      (node (ref "Hotbed") (pin "1") (pinfunction "1_1") (pintype "passive"))
      (node (ref "JS1") (pin "2") (pinfunction "2_2") (pintype "passive"))
      (node (ref "M1") (pin "2") (pinfunction "D_2") (pintype "passive"))
    )
    (net (code "47") (name "Net-(M2-D)") (class "Default")
      (node (ref "Hotend") (pin "1") (pinfunction "1_1") (pintype "passive"))
      (node (ref "JS2") (pin "2") (pinfunction "2_2") (pintype "passive"))
      (node (ref "M2") (pin "2") (pinfunction "D_2") (pintype "passive"))
    )
    (net (code "48") (name "Net-(M3-D)") (class "Default")
      (node (ref "FAN") (pin "1") (pinfunction "1_1") (pintype "passive"))
      (node (ref "FAN1") (pin "1") (pinfunction "1_1") (pintype "passive"))
      (node (ref "JS3") (pin "2") (pinfunction "2_2") (pintype "passive"))
      (node (ref "M3") (pin "2") (pinfunction "D_2") (pintype "passive"))
    )
    (net (code "49") (name "Net-(U8-XTAL1)") (class "Default")
      (node (ref "16M") (pin "2") (pinfunction "2_2") (pintype "passive"))
      (node (ref "C51") (pin "1") (pinfunction "1_1") (pintype "passive"))
      (node (ref "U8") (pin "8") (pinfunction "XTAL1_8") (pintype "passive"))
    )
    (net (code "50") (name "Net-(U8-XTAL2)") (class "Default")
      (node (ref "16M") (pin "1") (pinfunction "1_1") (pintype "passive"))
      (node (ref "C50") (pin "1") (pinfunction "1_1") (pintype "passive"))
      (node (ref "U8") (pin "7") (pinfunction "XTAL2_7") (pintype "passive"))
    )
    (net (code "51") (name "Net-(UP1-BST)") (class "Default")
      (node (ref "CP1") (pin "1") (pinfunction "1_1") (pintype "passive"))
      (node (ref "UP1") (pin "8") (pinfunction "BST_8") (pintype "passive"))
    )
    (net (code "52") (name "Net-(UP1-COMP)") (class "Default")
      (node (ref "CP3") (pin "2") (pinfunction "2_2") (pintype "passive"))
      (node (ref "UP1") (pin "3") (pinfunction "COMP_3") (pintype "passive"))
    )
    (net (code "53") (name "Net-(UP1-EN)") (class "Default")
      (node (ref "R_P1") (pin "2") (pinfunction "2_2") (pintype "passive"))
      (node (ref "R_P2") (pin "1") (pinfunction "1_1") (pintype "passive"))
      (node (ref "UP1") (pin "2") (pinfunction "EN_2") (pintype "passive"))
    )
    (net (code "54") (name "Net-(UP1-FB)") (class "Default")
      (node (ref "R_P4") (pin "1") (pinfunction "1_1") (pintype "passive"))
      (node (ref "R_P5") (pin "1") (pinfunction "1_1") (pintype "passive"))
      (node (ref "UP1") (pin "4") (pinfunction "FB_4") (pintype "passive"))
    )
    (net (code "55") (name "Net-(UP1-FREQ)") (class "Default")
      (node (ref "R_P3") (pin "1") (pinfunction "1_1") (pintype "passive"))
      (node (ref "UP1") (pin "6") (pinfunction "FREQ_6") (pintype "passive"))
    )
    (net (code "56") (name "Net-(UP1-SW)") (class "Default")
      (node (ref "CP1") (pin "2") (pinfunction "2_2") (pintype "passive"))
      (node (ref "DP1") (pin "2") (pinfunction "2_2") (pintype "passive"))
      (node (ref "LP1") (pin "2") (pinfunction "2_2") (pintype "passive"))
      (node (ref "UP1") (pin "1") (pinfunction "SW_1") (pintype "passive"))
    )
    (net (code "57") (name "UVCC") (class "Default")
      (node (ref "DP2") (pin "1") (pinfunction "1_1") (pintype "passive"))
      (node (ref "USB") (pin "5") (pinfunction "VCC_5") (pintype "passive"))
    )
    (net (code "58") (name "VCC") (class "Default")
      (node (ref "C41") (pin "1") (pinfunction "1_1") (pintype "passive"))
      (node (ref "C42") (pin "1") (pinfunction "1_1") (pintype "passive"))
      (node (ref "C43") (pin "1") (pinfunction "1_1") (pintype "passive"))
      (node (ref "C44") (pin "1") (pinfunction "1_1") (pintype "passive"))
      (node (ref "C45") (pin "1") (pinfunction "1_1") (pintype "passive"))
      (node (ref "DP2") (pin "2") (pinfunction "2_2") (pintype "passive"))
      (node (ref "EXP1") (pin "1") (pinfunction "1_1") (pintype "passive"))
      (node (ref "EXT-A2") (pin "1") (pinfunction "1_1") (pintype "passive"))
      (node (ref "FP1") (pin "2") (pinfunction "2_2") (pintype "passive"))
      (node (ref "ISP") (pin "2") (pinfunction "2_2") (pintype "passive"))
      (node (ref "LED2") (pin "2") (pinfunction "2_2") (pintype "passive"))
      (node (ref "R1") (pin "2") (pinfunction "2_2") (pintype "passive"))
      (node (ref "R2") (pin "2") (pinfunction "2_2") (pintype "passive"))
      (node (ref "R26") (pin "2") (pinfunction "2_2") (pintype "passive"))
      (node (ref "R3") (pin "2") (pinfunction "2_2") (pintype "passive"))
      (node (ref "R4") (pin "2") (pinfunction "2_2") (pintype "passive"))
      (node (ref "R5") (pin "2") (pinfunction "2_2") (pintype "passive"))
      (node (ref "U1") (pin "20") (pinfunction "VCC_20") (pintype "power_in"))
      (node (ref "U1") (pin "4") (pinfunction "VCCIO_4") (pintype "power_in"))
      (node (ref "U8") (pin "17") (pinfunction "VCC_17") (pintype "power_in"))
      (node (ref "U8") (pin "27") (pinfunction "AVCC_27") (pintype "power_in"))
      (node (ref "U8") (pin "29") (pinfunction "AREF_29") (pintype "passive"))
      (node (ref "U8") (pin "38") (pinfunction "VCC_38") (pintype "power_in"))
      (node (ref "U8") (pin "5") (pinfunction "VCC_5") (pintype "power_in"))
    )
    (net (code "59") (name "VDD") (class "Default")
      (node (ref "C31") (pin "1") (pinfunction "1_1") (pintype "passive"))
      (node (ref "TF") (pin "4") (pinfunction "VCC_4") (pintype "passive"))
      (node (ref "U1") (pin "17") (pinfunction "3V3OUT_17") (pintype "output"))
      (node (ref "U2") (pin "20") (pinfunction "VCC_20") (pintype "power_in"))
    )
    (net (code "60") (name "VMOT") (class "Default")
      (node (ref "C28") (pin "1") (pinfunction "1_1") (pintype "passive"))
      (node (ref "C30") (pin "1") (pinfunction "1_1") (pintype "passive"))
      (node (ref "FAN") (pin "2") (pinfunction "2_2") (pintype "passive"))
      (node (ref "FAN1") (pin "2") (pinfunction "2_2") (pintype "passive"))
      (node (ref "Hotbed") (pin "2") (pinfunction "2_2") (pintype "passive"))
      (node (ref "Hotend") (pin "2") (pinfunction "2_2") (pintype "passive"))
      (node (ref "PWR") (pin "2") (pinfunction "2_2") (pintype "passive"))
      (node (ref "R_P1") (pin "1") (pinfunction "1_1") (pintype "passive"))
      (node (ref "UP1") (pin "7") (pinfunction "VIN_7") (pintype "passive"))
    )
    (net (code "61") (name "unconnected-(TF-DAT1-Pad8)") (class "Default")
      (node (ref "TF") (pin "8") (pinfunction "DAT1_8") (pintype "passive+no_connect"))
    )
    (net (code "62") (name "unconnected-(TF-DAT2-Pad1)") (class "Default")
      (node (ref "TF") (pin "1") (pinfunction "DAT2_1") (pintype "passive+no_connect"))
    )
    (net (code "63") (name "unconnected-(U1-CBUS0-Pad23)") (class "Default")
      (node (ref "U1") (pin "23") (pinfunction "CBUS0_23") (pintype "bidirectional+no_connect"))
    )
    (net (code "64") (name "unconnected-(U1-CBUS1-Pad22)") (class "Default")
      (node (ref "U1") (pin "22") (pinfunction "CBUS1_22") (pintype "bidirectional+no_connect"))
    )
    (net (code "65") (name "unconnected-(U1-CBUS2-Pad13)") (class "Default")
      (node (ref "U1") (pin "13") (pinfunction "CBUS2_13") (pintype "bidirectional+no_connect"))
    )
    (net (code "66") (name "unconnected-(U1-CBUS3-Pad14)") (class "Default")
      (node (ref "U1") (pin "14") (pinfunction "CBUS3_14") (pintype "bidirectional+no_connect"))
    )
    (net (code "67") (name "unconnected-(U1-CBUS4-Pad12)") (class "Default")
      (node (ref "U1") (pin "12") (pinfunction "CBUS4_12") (pintype "bidirectional+no_connect"))
    )
    (net (code "68") (name "unconnected-(U1-OSCI-Pad27)") (class "Default")
      (node (ref "U1") (pin "27") (pinfunction "OSCI_27") (pintype "power_in+no_connect"))
    )
    (net (code "69") (name "unconnected-(U1-OSCO-Pad28)") (class "Default")
      (node (ref "U1") (pin "28") (pinfunction "OSCO_28") (pintype "power_in+no_connect"))
    )
    (net (code "70") (name "unconnected-(U1-~{CTS}-Pad11)") (class "Default")
      (node (ref "U1") (pin "11") (pinfunction "~{CTS}_11") (pintype "input+no_connect"))
    )
    (net (code "71") (name "unconnected-(U1-~{DCD}-Pad10)") (class "Default")
      (node (ref "U1") (pin "10") (pinfunction "~{DCD}_10") (pintype "input+no_connect"))
    )
    (net (code "72") (name "unconnected-(U1-~{DSR}-Pad9)") (class "Default")
      (node (ref "U1") (pin "9") (pinfunction "~{DSR}_9") (pintype "input+no_connect"))
    )
    (net (code "73") (name "unconnected-(U1-~{RESET}-Pad19)") (class "Default")
      (node (ref "U1") (pin "19") (pinfunction "~{RESET}_19") (pintype "input+no_connect"))
    )
    (net (code "74") (name "unconnected-(U1-~{RI}-Pad6)") (class "Default")
      (node (ref "U1") (pin "6") (pinfunction "~{RI}_6") (pintype "input+no_connect"))
    )
    (net (code "75") (name "unconnected-(U1-~{RTS}-Pad3)") (class "Default")
      (node (ref "U1") (pin "3") (pinfunction "~{RTS}_3") (pintype "output+no_connect"))
    )
    (net (code "76") (name "unconnected-(U2B-A5-Pad6)") (class "Default")
      (node (ref "U2") (pin "6") (pinfunction "A5_6") (pintype "input+no_connect"))
    )
    (net (code "77") (name "unconnected-(U2B-A6-Pad7)") (class "Default")
      (node (ref "U2") (pin "7") (pinfunction "A6_7") (pintype "input+no_connect"))
    )
    (net (code "78") (name "unconnected-(U2B-A7-Pad8)") (class "Default")
      (node (ref "U2") (pin "8") (pinfunction "A7_8") (pintype "input+no_connect"))
    )
    (net (code "79") (name "unconnected-(U2B-A8-Pad9)") (class "Default")
      (node (ref "U2") (pin "9") (pinfunction "A8_9") (pintype "input+no_connect"))
    )
    (net (code "80") (name "unconnected-(U2B-Y5-Pad14)") (class "Default")
      (node (ref "U2") (pin "14") (pinfunction "Y5_14") (pintype "output+no_connect"))
    )
    (net (code "81") (name "unconnected-(U2B-Y6-Pad13)") (class "Default")
      (node (ref "U2") (pin "13") (pinfunction "Y6_13") (pintype "output+no_connect"))
    )
    (net (code "82") (name "unconnected-(U2B-Y7-Pad12)") (class "Default")
      (node (ref "U2") (pin "12") (pinfunction "Y7_12") (pintype "output+no_connect"))
    )
    (net (code "83") (name "unconnected-(U2B-Y8-Pad11)") (class "Default")
      (node (ref "U2") (pin "11") (pinfunction "Y8_11") (pintype "output+no_connect"))
    )
    (net (code "84") (name "unconnected-(USB-ID-Pad2)") (class "Default")
      (node (ref "USB") (pin "2") (pinfunction "ID_2") (pintype "passive"))
    )
    (net (code "85") (name "unconnected-(USB-SH-Pad0)") (class "Default")
      (node (ref "USB") (pin "0") (pinfunction "SH_0") (pintype "passive+no_connect"))
    )
  )
)
